# SensorLTR390.net
KiCad netlist of a schematic drawn in Altium Designer
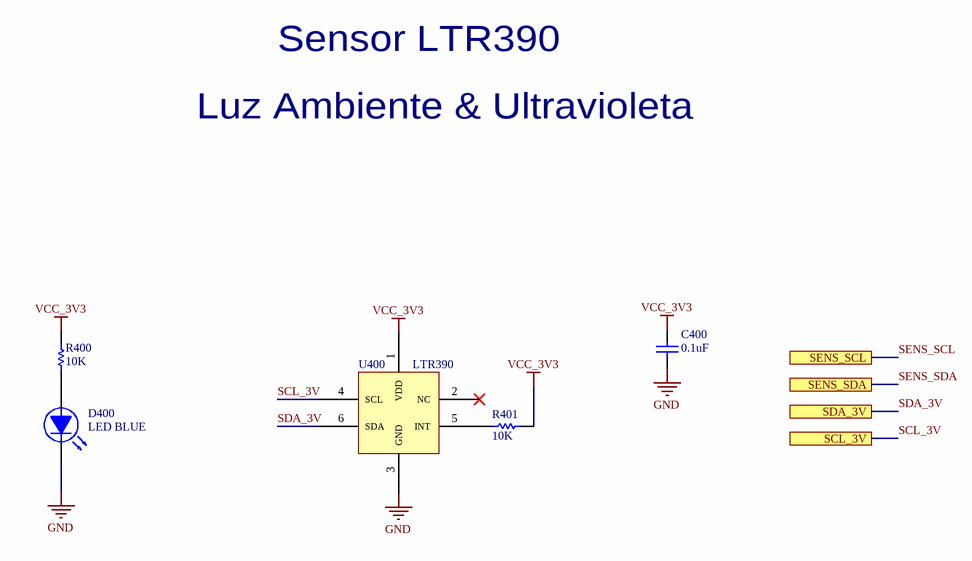
[diagram p0: SensorLTR390.SchDoc]

(export (version "E")
  (design (tool "Eeschema 10.0.6"))
  (components
    (comp (ref "C400")
      (value "0.1uF")
      (footprint "CAP_CER_0603")
      (libsource (lib "PCB_TCC") (part "CAP_CER_0.1uF_0603"))
    )
    (comp (ref "D400")
      (value "LED BLUE")
      (footprint "LED_BLUE_SMD_0603")
      (libsource (lib "PCB_TCC") (part "LED_BLUE_SMD_0603"))
    )
    (comp (ref "R400") (value "10K") (footprint "RES_0603") (libsource (lib "PCB_TCC") (part "RES_10K_0603")))
    (comp (ref "R401") (value "10K") (footprint "RES_0603") (libsource (lib "PCB_TCC") (part "RES_10K_0603")))
    (comp (ref "U400") (value "LTR390") (footprint "LTR390") (libsource (lib "PCB_TCC") (part "LTR390")))
  )
  (nets
    (net (code "1") (name "/SCL_3V") (class "Default")
      (node (ref "U400") (pin "4") (pinfunction "SCL_4") (pintype "passive"))
    )
    (net (code "2") (name "/SDA_3V") (class "Default")
      (node (ref "U400") (pin "6") (pinfunction "SDA_6") (pintype "passive"))
    )
    (net (code "5") (name "GND") (class "Default")
      (node (ref "C400") (pin "1") (pinfunction "1_1") (pintype "passive"))
      (node (ref "D400") (pin "K") (pinfunction "K_K") (pintype "passive"))
      (node (ref "U400") (pin "3") (pinfunction "GND_3") (pintype "passive"))
    )
    (net (code "6") (name "Net-(D400-PadA)") (class "Default")
      (node (ref "D400") (pin "A") (pinfunction "A_A") (pintype "passive"))
      (node (ref "R400") (pin "1") (pinfunction "1_1") (pintype "passive"))
    )
    (net (code "7") (name "Net-(U400-INT)") (class "Default")
      (node (ref "R401") (pin "1") (pinfunction "1_1") (pintype "passive"))
      (node (ref "U400") (pin "5") (pinfunction "INT_5") (pintype "passive"))
    )
    (net (code "8") (name "VCC_3V3") (class "Default")
      (node (ref "C400") (pin "2") (pinfunction "2_2") (pintype "passive"))
      (node (ref "R400") (pin "2") (pinfunction "2_2") (pintype "passive"))
      (node (ref "R401") (pin "2") (pinfunction "2_2") (pintype "passive"))
      (node (ref "U400") (pin "1") (pinfunction "VDD_1") (pintype "passive"))
    )
    (net (code "9") (name "unconnected-(U400-NC-Pad2)") (class "Default")
      (node (ref "U400") (pin "2") (pinfunction "NC_2") (pintype "passive+no_connect"))
    )
  )
)
